# booz_power_board.net
KiCad netlist of a schematic drawn in EAGLE
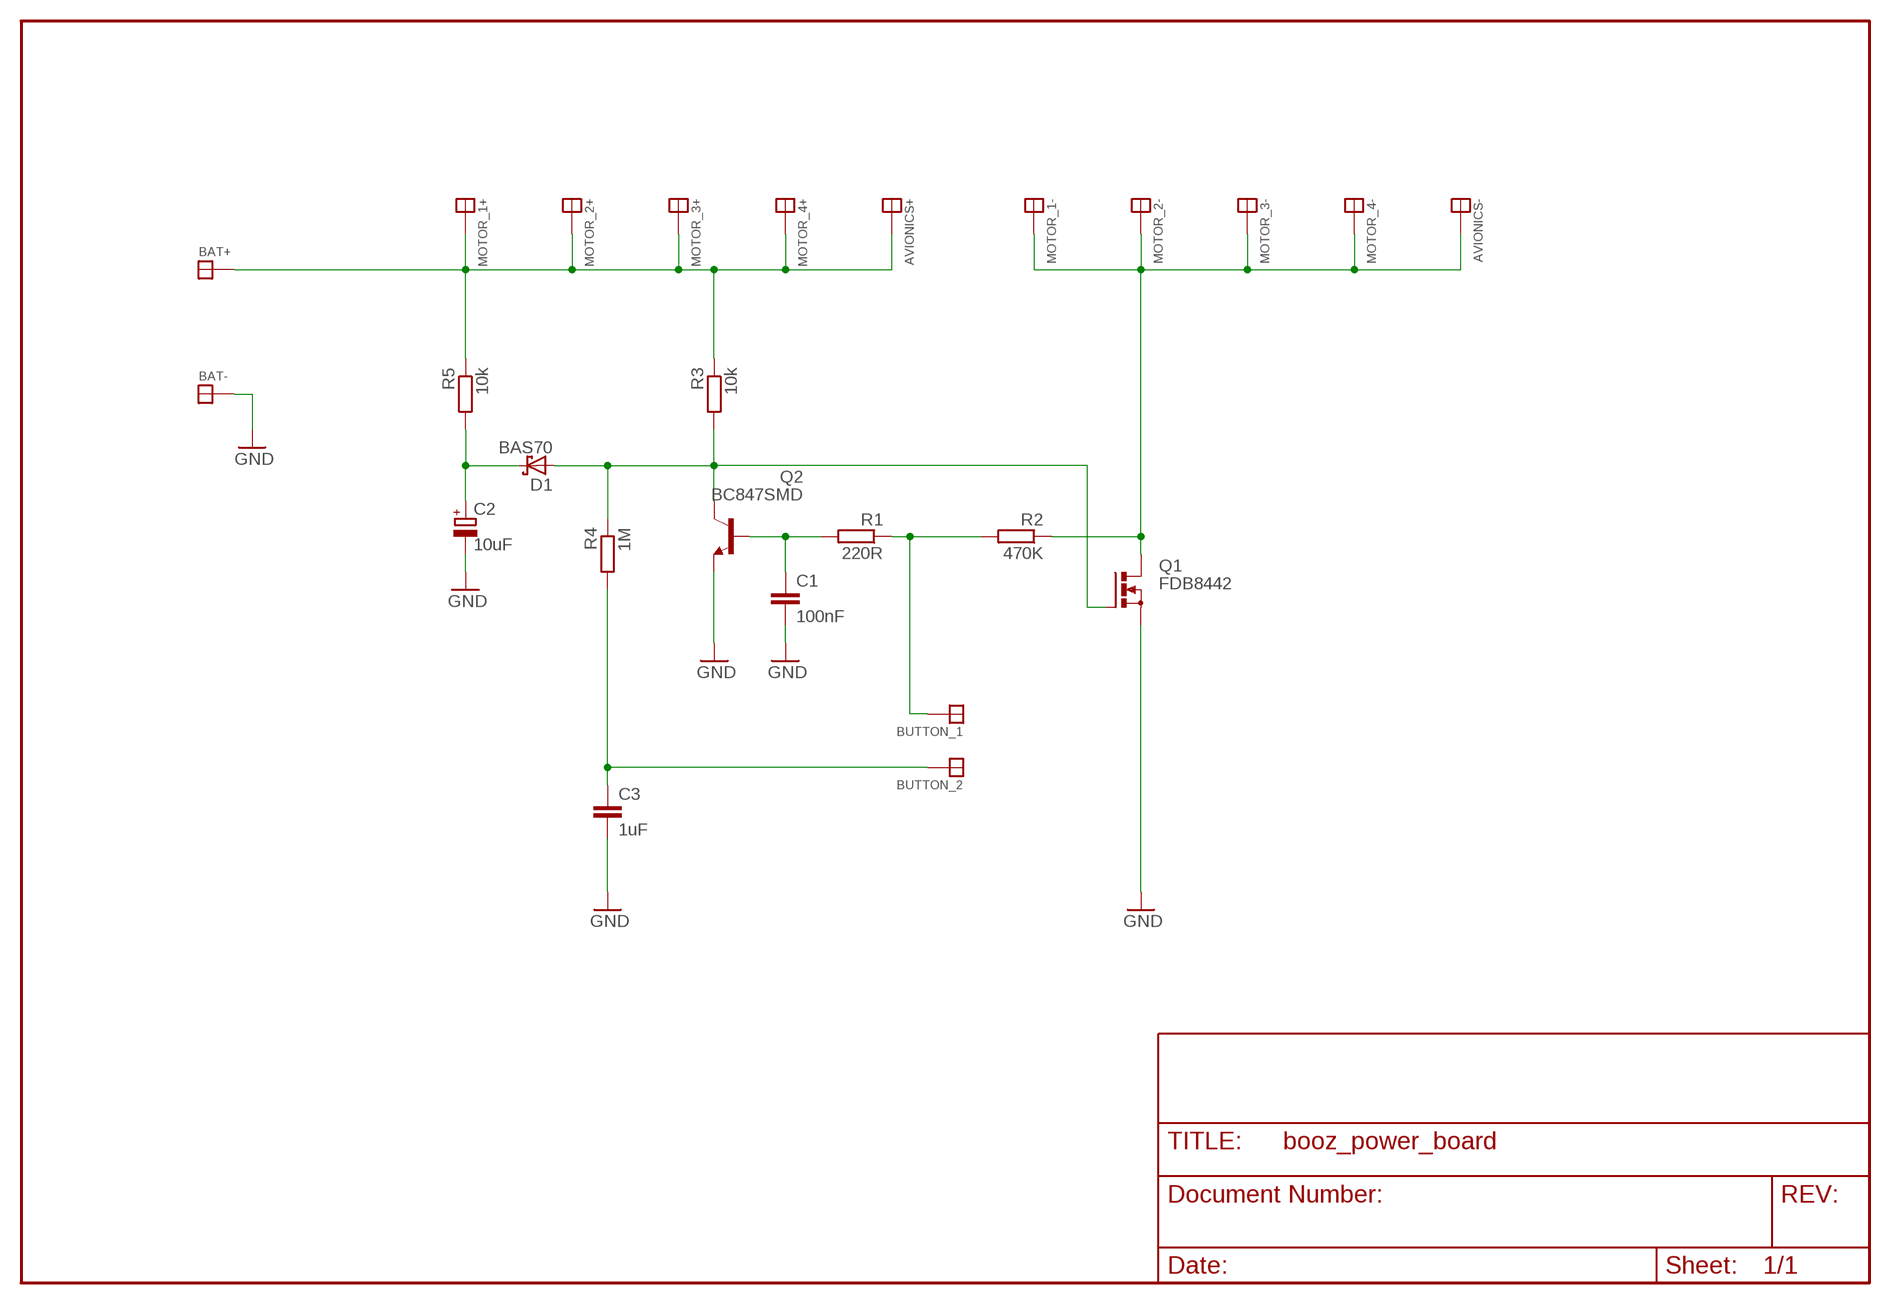
[diagram p0: schematic, sheet 1]

(export (version "E")
  (design (tool "Eeschema 10.0.6"))
  (components
    (comp (ref "AVIONICS+")
      (value "SOLDER_PAD100_50")
      (footprint "eagle-import:SOLDER_PAD_100_50")
      (libsource (lib "eagle-import") (part "SOLDER_PAD100_50"))
    )
    (comp (ref "AVIONICS-")
      (value "SOLDER_PAD100_50")
      (footprint "eagle-import:SOLDER_PAD_100_50")
      (libsource (lib "eagle-import") (part "SOLDER_PAD100_50"))
    )
    (comp (ref "BAT+")
      (value "SOLDER_PAD100_50")
      (footprint "eagle-import:SOLDER_PAD_100_50")
      (libsource (lib "eagle-import") (part "SOLDER_PAD100_50"))
    )
    (comp (ref "BAT-")
      (value "SOLDER_PAD100_50")
      (footprint "eagle-import:SOLDER_PAD_100_50")
      (libsource (lib "eagle-import") (part "SOLDER_PAD100_50"))
    )
    (comp (ref "BUTTON_1")
      (value "SOLDER_PAD100_50")
      (footprint "eagle-import:SOLDER_PAD_100_50")
      (libsource (lib "eagle-import") (part "SOLDER_PAD100_50"))
    )
    (comp (ref "BUTTON_2")
      (value "SOLDER_PAD100_50")
      (footprint "eagle-import:SOLDER_PAD_100_50")
      (libsource (lib "eagle-import") (part "SOLDER_PAD100_50"))
    )
    (comp (ref "C1")
      (value "100nF")
      (footprint "eagle-import:C0603")
      (libsource (lib "eagle-import") (part "C-EUC0603"))
    )
    (comp (ref "C2")
      (value "10uF")
      (footprint "eagle-import:SMC_A")
      (libsource (lib "eagle-import") (part "CPOL-EUSMCA"))
    )
    (comp (ref "C3")
      (value "1uF")
      (footprint "eagle-import:C0603")
      (libsource (lib "eagle-import") (part "C-EUC0603"))
    )
    (comp (ref "D1")
      (value "BAS70")
      (footprint "eagle-import:SOT23")
      (libsource (lib "eagle-import") (part "BAS70"))
    )
    (comp (ref "MOTOR_1+")
      (value "SOLDER_PAD100_50")
      (footprint "eagle-import:SOLDER_PAD_100_50")
      (libsource (lib "eagle-import") (part "SOLDER_PAD100_50"))
    )
    (comp (ref "MOTOR_1-")
      (value "SOLDER_PAD100_50")
      (footprint "eagle-import:SOLDER_PAD_100_50")
      (libsource (lib "eagle-import") (part "SOLDER_PAD100_50"))
    )
    (comp (ref "MOTOR_2+")
      (value "SOLDER_PAD100_50")
      (footprint "eagle-import:SOLDER_PAD_100_50")
      (libsource (lib "eagle-import") (part "SOLDER_PAD100_50"))
    )
    (comp (ref "MOTOR_2-")
      (value "SOLDER_PAD100_50")
      (footprint "eagle-import:SOLDER_PAD_100_50")
      (libsource (lib "eagle-import") (part "SOLDER_PAD100_50"))
    )
    (comp (ref "MOTOR_3+")
      (value "SOLDER_PAD100_50")
      (footprint "eagle-import:SOLDER_PAD_100_50")
      (libsource (lib "eagle-import") (part "SOLDER_PAD100_50"))
    )
    (comp (ref "MOTOR_3-")
      (value "SOLDER_PAD100_50")
      (footprint "eagle-import:SOLDER_PAD_100_50")
      (libsource (lib "eagle-import") (part "SOLDER_PAD100_50"))
    )
    (comp (ref "MOTOR_4+")
      (value "SOLDER_PAD100_50")
      (footprint "eagle-import:SOLDER_PAD_100_50")
      (libsource (lib "eagle-import") (part "SOLDER_PAD100_50"))
    )
    (comp (ref "MOTOR_4-")
      (value "SOLDER_PAD100_50")
      (footprint "eagle-import:SOLDER_PAD_100_50")
      (libsource (lib "eagle-import") (part "SOLDER_PAD100_50"))
    )
    (comp (ref "Q1")
      (value "FDB8442")
      (footprint "eagle-import:TO263")
      (libsource (lib "eagle-import") (part "FDB8442"))
    )
    (comp (ref "Q2")
      (value "BC847SMD")
      (footprint "eagle-import:SOT23")
      (libsource (lib "eagle-import") (part "BC847SMD"))
    )
    (comp (ref "R1")
      (value "220R")
      (footprint "eagle-import:R1206")
      (libsource (lib "eagle-import") (part "R-EU_R1206"))
    )
    (comp (ref "R2")
      (value "470K")
      (footprint "eagle-import:R0603")
      (libsource (lib "eagle-import") (part "R-EU_R0603"))
    )
    (comp (ref "R3")
      (value "10k")
      (footprint "eagle-import:R1206")
      (libsource (lib "eagle-import") (part "R-EU_R1206"))
    )
    (comp (ref "R4")
      (value "1M")
      (footprint "eagle-import:R0603")
      (libsource (lib "eagle-import") (part "R-EU_R0603"))
    )
    (comp (ref "R5")
      (value "10k")
      (footprint "eagle-import:R0603")
      (libsource (lib "eagle-import") (part "R-EU_R0603"))
    )
  )
  (nets
    (net (code "1") (name "GND") (class "Default")
      (node (ref "BAT-") (pin "P$1") (pinfunction "P$1_P$1") (pintype "bidirectional"))
      (node (ref "C1") (pin "2") (pinfunction "2_2") (pintype "passive"))
      (node (ref "C2") (pin "-") (pinfunction "-_-") (pintype "passive"))
      (node (ref "C3") (pin "2") (pinfunction "2_2") (pintype "passive"))
      (node (ref "Q1") (pin "2") (pinfunction "S_2") (pintype "passive"))
      (node (ref "Q2") (pin "2") (pinfunction "E_2") (pintype "passive"))
    )
    (net (code "2") (name "Net-(AVIONICS+-PadP$1)") (class "Default")
      (node (ref "AVIONICS+") (pin "P$1") (pinfunction "P$1_P$1") (pintype "bidirectional"))
      (node (ref "BAT+") (pin "P$1") (pinfunction "P$1_P$1") (pintype "bidirectional"))
      (node (ref "MOTOR_1+") (pin "P$1") (pinfunction "P$1_P$1") (pintype "bidirectional"))
      (node (ref "MOTOR_2+") (pin "P$1") (pinfunction "P$1_P$1") (pintype "bidirectional"))
      (node (ref "MOTOR_3+") (pin "P$1") (pinfunction "P$1_P$1") (pintype "bidirectional"))
      (node (ref "MOTOR_4+") (pin "P$1") (pinfunction "P$1_P$1") (pintype "bidirectional"))
      (node (ref "R3") (pin "1") (pinfunction "1_1") (pintype "passive"))
      (node (ref "R5") (pin "1") (pinfunction "1_1") (pintype "passive"))
    )
    (net (code "3") (name "Net-(BUTTON_1-PadP$1)") (class "Default")
      (node (ref "BUTTON_1") (pin "P$1") (pinfunction "P$1_P$1") (pintype "bidirectional"))
      (node (ref "R1") (pin "1") (pinfunction "1_1") (pintype "passive"))
      (node (ref "R2") (pin "2") (pinfunction "2_2") (pintype "passive"))
    )
    (net (code "4") (name "Net-(BUTTON_2-PadP$1)") (class "Default")
      (node (ref "BUTTON_2") (pin "P$1") (pinfunction "P$1_P$1") (pintype "bidirectional"))
      (node (ref "C3") (pin "1") (pinfunction "1_1") (pintype "passive"))
      (node (ref "R4") (pin "2") (pinfunction "2_2") (pintype "passive"))
    )
    (net (code "5") (name "Net-(D1-A)") (class "Default")
      (node (ref "D1") (pin "1") (pinfunction "A_1") (pintype "passive"))
      (node (ref "Q1") (pin "1") (pinfunction "G_1") (pintype "passive"))
      (node (ref "Q2") (pin "3") (pinfunction "C_3") (pintype "passive"))
      (node (ref "R3") (pin "2") (pinfunction "2_2") (pintype "passive"))
      (node (ref "R4") (pin "1") (pinfunction "1_1") (pintype "passive"))
    )
    (net (code "6") (name "Net-(D1-C)") (class "Default")
      (node (ref "C2") (pin "+") (pinfunction "+_+") (pintype "passive"))
      (node (ref "D1") (pin "3") (pinfunction "C_3") (pintype "passive"))
      (node (ref "R5") (pin "2") (pinfunction "2_2") (pintype "passive"))
    )
    (net (code "7") (name "Net-(Q1-D)") (class "Default")
      (node (ref "AVIONICS-") (pin "P$1") (pinfunction "P$1_P$1") (pintype "bidirectional"))
      (node (ref "MOTOR_1-") (pin "P$1") (pinfunction "P$1_P$1") (pintype "bidirectional"))
      (node (ref "MOTOR_2-") (pin "P$1") (pinfunction "P$1_P$1") (pintype "bidirectional"))
      (node (ref "MOTOR_3-") (pin "P$1") (pinfunction "P$1_P$1") (pintype "bidirectional"))
      (node (ref "MOTOR_4-") (pin "P$1") (pinfunction "P$1_P$1") (pintype "bidirectional"))
      (node (ref "Q1") (pin "3") (pinfunction "D_3") (pintype "passive"))
      (node (ref "R2") (pin "1") (pinfunction "1_1") (pintype "passive"))
    )
    (net (code "8") (name "Net-(Q2-B)") (class "Default")
      (node (ref "C1") (pin "1") (pinfunction "1_1") (pintype "passive"))
      (node (ref "Q2") (pin "1") (pinfunction "B_1") (pintype "passive"))
      (node (ref "R1") (pin "2") (pinfunction "2_2") (pintype "passive"))
    )
  )
)
